# Power_Distro_Board_V5.net
KiCad netlist of a schematic drawn in EAGLE
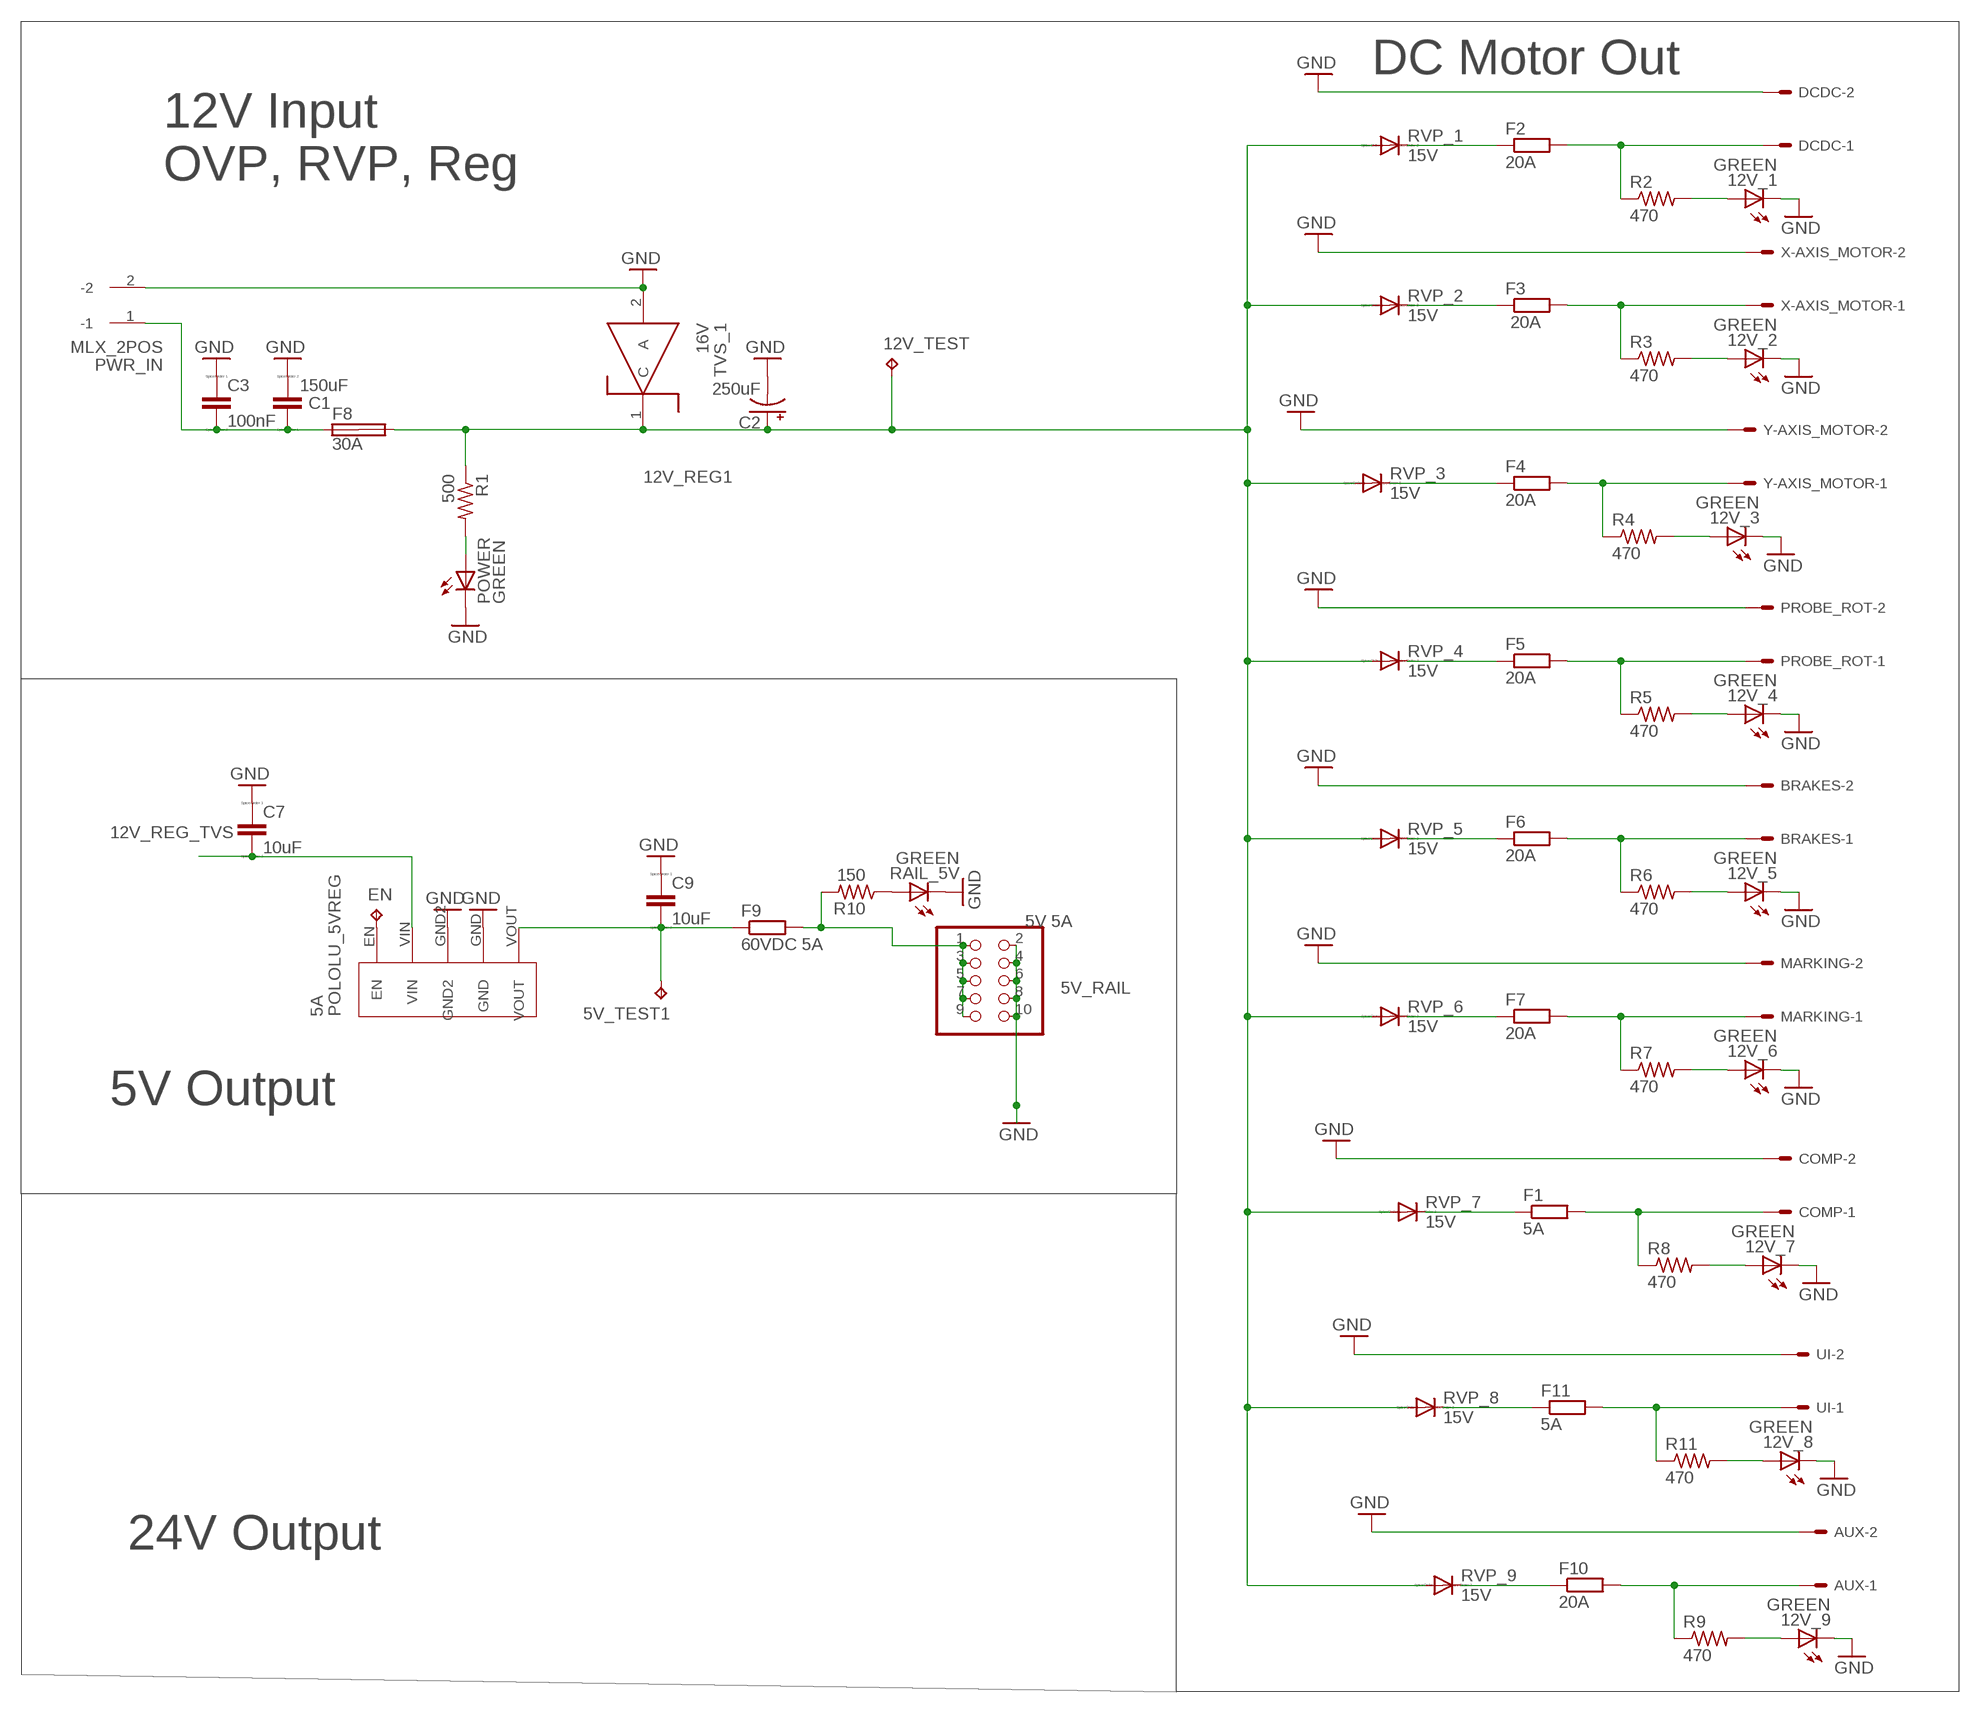
[diagram p0: schematic, sheet 1]

(export (version "E")
  (design (tool "Eeschema 10.0.6"))
  (components
    (comp (ref "5A")
      (value "POLOLU_5VREG")
      (footprint "eagle-import:SIP5")
      (libsource (lib "eagle-import") (part "POLOLU_5VREG"))
    )
    (comp (ref "5V_RAIL")
      (value "5V 5A")
      (footprint "eagle-import:2X05")
      (libsource (lib "eagle-import") (part "PINHD-2X5"))
    )
    (comp (ref "5V_TEST1")
      (value "TPPAD1-13")
      (footprint "eagle-import:P1-13")
      (libsource (lib "eagle-import") (part "TPPAD1-13"))
    )
    (comp (ref "12V_1")
      (value "GREEN")
      (footprint "eagle-import:SML1206")
      (libsource (lib "eagle-import") (part "LEDSML1206"))
    )
    (comp (ref "12V_2")
      (value "GREEN")
      (footprint "eagle-import:SML1206")
      (libsource (lib "eagle-import") (part "LEDSML1206"))
    )
    (comp (ref "12V_3")
      (value "GREEN")
      (footprint "eagle-import:SML1206")
      (libsource (lib "eagle-import") (part "LEDSML1206"))
    )
    (comp (ref "12V_4")
      (value "GREEN")
      (footprint "eagle-import:SML1206")
      (libsource (lib "eagle-import") (part "LEDSML1206"))
    )
    (comp (ref "12V_5")
      (value "GREEN")
      (footprint "eagle-import:SML1206")
      (libsource (lib "eagle-import") (part "LEDSML1206"))
    )
    (comp (ref "12V_6")
      (value "GREEN")
      (footprint "eagle-import:SML1206")
      (libsource (lib "eagle-import") (part "LEDSML1206"))
    )
    (comp (ref "12V_7")
      (value "GREEN")
      (footprint "eagle-import:SML1206")
      (libsource (lib "eagle-import") (part "LEDSML1206"))
    )
    (comp (ref "12V_8")
      (value "GREEN")
      (footprint "eagle-import:SML1206")
      (libsource (lib "eagle-import") (part "LEDSML1206"))
    )
    (comp (ref "12V_9")
      (value "GREEN")
      (footprint "eagle-import:SML1206")
      (libsource (lib "eagle-import") (part "LEDSML1206"))
    )
    (comp (ref "12V_TEST")
      (value "TPPAD1-13")
      (footprint "eagle-import:P1-13")
      (libsource (lib "eagle-import") (part "TPPAD1-13"))
    )
    (comp (ref "AUX")
      (value "555X-2V")
      (footprint "eagle-import:5566-2")
      (libsource (lib "eagle-import") (part "555X-2V"))
    )
    (comp (ref "BRAKES")
      (value "555X-2V")
      (footprint "eagle-import:5566-2")
      (libsource (lib "eagle-import") (part "555X-2V"))
    )
    (comp (ref "C1")
      (value "150uF")
      (footprint "eagle-import:C1210")
      (libsource (lib "eagle-import") (part "CC1210"))
    )
    (comp (ref "C2")
      (value "250uF")
      (footprint "eagle-import:CPOL-RADIAL-5MM-10MM")
      (libsource (lib "eagle-import") (part "ALUM_ELEC_RADIAL"))
    )
    (comp (ref "C3")
      (value "100nF")
      (footprint "eagle-import:C1210")
      (libsource (lib "eagle-import") (part "CC1210"))
    )
    (comp (ref "C7")
      (value "10uF")
      (footprint "eagle-import:C1210")
      (libsource (lib "eagle-import") (part "CC1210"))
    )
    (comp (ref "C9")
      (value "10uF")
      (footprint "eagle-import:C1210")
      (libsource (lib "eagle-import") (part "CC1210"))
    )
    (comp (ref "COMP")
      (value "555X-2V")
      (footprint "eagle-import:5566-2")
      (libsource (lib "eagle-import") (part "555X-2V"))
    )
    (comp (ref "DCDC")
      (value "555X-2V")
      (footprint "eagle-import:5566-2")
      (libsource (lib "eagle-import") (part "555X-2V"))
    )
    (comp (ref "EN")
      (value "TPPAD1-13")
      (footprint "eagle-import:P1-13")
      (libsource (lib "eagle-import") (part "TPPAD1-13"))
    )
    (comp (ref "F1")
      (value "5A")
      (footprint "eagle-import:M1206")
      (libsource (lib "eagle-import") (part "R-EU_M1206"))
    )
    (comp (ref "F2")
      (value "20A")
      (footprint "eagle-import:M1206")
      (libsource (lib "eagle-import") (part "R-EU_M1206"))
    )
    (comp (ref "F3")
      (value "20A")
      (footprint "eagle-import:M1206")
      (libsource (lib "eagle-import") (part "R-EU_M1206"))
    )
    (comp (ref "F4")
      (value "20A")
      (footprint "eagle-import:M1206")
      (libsource (lib "eagle-import") (part "R-EU_M1206"))
    )
    (comp (ref "F5")
      (value "20A")
      (footprint "eagle-import:M1206")
      (libsource (lib "eagle-import") (part "R-EU_M1206"))
    )
    (comp (ref "F6")
      (value "20A")
      (footprint "eagle-import:M1206")
      (libsource (lib "eagle-import") (part "R-EU_M1206"))
    )
    (comp (ref "F7")
      (value "20A")
      (footprint "eagle-import:M1206")
      (libsource (lib "eagle-import") (part "R-EU_M1206"))
    )
    (comp (ref "F8")
      (value "30A")
      (footprint "eagle-import:SHK20L")
      (libsource (lib "eagle-import") (part "SHK20L"))
    )
    (comp (ref "F9")
      (value "60VDC 5A")
      (footprint "eagle-import:M1206")
      (libsource (lib "eagle-import") (part "R-EU_M1206"))
    )
    (comp (ref "F10")
      (value "20A")
      (footprint "eagle-import:M1206")
      (libsource (lib "eagle-import") (part "R-EU_M1206"))
    )
    (comp (ref "F11")
      (value "5A")
      (footprint "eagle-import:M1206")
      (libsource (lib "eagle-import") (part "R-EU_M1206"))
    )
    (comp (ref "MARKING")
      (value "555X-2V")
      (footprint "eagle-import:5566-2")
      (libsource (lib "eagle-import") (part "555X-2V"))
    )
    (comp (ref "POWER")
      (value "GREEN")
      (footprint "eagle-import:SML1206")
      (libsource (lib "eagle-import") (part "LEDSML1206"))
    )
    (comp (ref "PROBE_ROT")
      (value "555X-2V")
      (footprint "eagle-import:5566-2")
      (libsource (lib "eagle-import") (part "555X-2V"))
    )
    (comp (ref "PWR_IN")
      (value "MLX_2POS")
      (footprint "eagle-import:.084MLX")
      (libsource (lib "eagle-import") (part "MLX_2POS"))
    )
    (comp (ref "R1")
      (value "500")
      (footprint "eagle-import:R1206")
      (libsource (lib "eagle-import") (part "R-US_R1206"))
    )
    (comp (ref "R2")
      (value "470")
      (footprint "eagle-import:R1206")
      (libsource (lib "eagle-import") (part "R-US_R1206"))
    )
    (comp (ref "R3")
      (value "470")
      (footprint "eagle-import:R1206")
      (libsource (lib "eagle-import") (part "R-US_R1206"))
    )
    (comp (ref "R4")
      (value "470")
      (footprint "eagle-import:R1206")
      (libsource (lib "eagle-import") (part "R-US_R1206"))
    )
    (comp (ref "R5")
      (value "470")
      (footprint "eagle-import:R1206")
      (libsource (lib "eagle-import") (part "R-US_R1206"))
    )
    (comp (ref "R6")
      (value "470")
      (footprint "eagle-import:R1206")
      (libsource (lib "eagle-import") (part "R-US_R1206"))
    )
    (comp (ref "R7")
      (value "470")
      (footprint "eagle-import:R1206")
      (libsource (lib "eagle-import") (part "R-US_R1206"))
    )
    (comp (ref "R8")
      (value "470")
      (footprint "eagle-import:R1206")
      (libsource (lib "eagle-import") (part "R-US_R1206"))
    )
    (comp (ref "R9")
      (value "470")
      (footprint "eagle-import:R1206")
      (libsource (lib "eagle-import") (part "R-US_R1206"))
    )
    (comp (ref "R10")
      (value "150")
      (footprint "eagle-import:R1206")
      (libsource (lib "eagle-import") (part "R-US_R1206"))
    )
    (comp (ref "R11")
      (value "470")
      (footprint "eagle-import:R1206")
      (libsource (lib "eagle-import") (part "R-US_R1206"))
    )
    (comp (ref "RAIL_5V")
      (value "GREEN")
      (footprint "eagle-import:SML1206")
      (libsource (lib "eagle-import") (part "LEDSML1206"))
    )
    (comp (ref "RVP_1")
      (value "15V")
      (footprint "eagle-import:TO220ACS")
      (libsource (lib "eagle-import") (part "BYT08P"))
    )
    (comp (ref "RVP_2")
      (value "15V")
      (footprint "eagle-import:TO220ACS")
      (libsource (lib "eagle-import") (part "BYT08P"))
    )
    (comp (ref "RVP_3")
      (value "15V")
      (footprint "eagle-import:TO220ACS")
      (libsource (lib "eagle-import") (part "BYT08P"))
    )
    (comp (ref "RVP_4")
      (value "15V")
      (footprint "eagle-import:TO220ACS")
      (libsource (lib "eagle-import") (part "BYT08P"))
    )
    (comp (ref "RVP_5")
      (value "15V")
      (footprint "eagle-import:TO220ACS")
      (libsource (lib "eagle-import") (part "BYT08P"))
    )
    (comp (ref "RVP_6")
      (value "15V")
      (footprint "eagle-import:TO220ACS")
      (libsource (lib "eagle-import") (part "BYT08P"))
    )
    (comp (ref "RVP_7")
      (value "15V")
      (footprint "eagle-import:TO220ACS")
      (libsource (lib "eagle-import") (part "BYT08P"))
    )
    (comp (ref "RVP_8")
      (value "15V")
      (footprint "eagle-import:TO220ACS")
      (libsource (lib "eagle-import") (part "BYT08P"))
    )
    (comp (ref "RVP_9")
      (value "15V")
      (footprint "eagle-import:TO220ACS")
      (libsource (lib "eagle-import") (part "BYT08P"))
    )
    (comp (ref "TVS_1")
      (value "16V")
      (footprint "eagle-import:DO-214AC")
      (libsource (lib "eagle-import") (part "SMAJ26A_TVSSMA"))
    )
    (comp (ref "UI")
      (value "555X-2V")
      (footprint "eagle-import:5566-2")
      (libsource (lib "eagle-import") (part "555X-2V"))
    )
    (comp (ref "X-AXIS_MOTOR")
      (value "555X-2V")
      (footprint "eagle-import:5566-2")
      (libsource (lib "eagle-import") (part "555X-2V"))
    )
    (comp (ref "Y-AXIS_MOTOR")
      (value "555X-2V")
      (footprint "eagle-import:5566-2")
      (libsource (lib "eagle-import") (part "555X-2V"))
    )
  )
  (nets
    (net (code "1") (name "/12V_REG1") (class "Default")
      (node (ref "12V_TEST") (pin "TP") (pinfunction "TP_TP") (pintype "input"))
      (node (ref "C2") (pin "+") (pinfunction "+_+") (pintype "passive"))
      (node (ref "F8") (pin "2A") (pinfunction "2A_2A") (pintype "passive"))
      (node (ref "R1") (pin "1") (pinfunction "1_1") (pintype "passive"))
      (node (ref "RVP_1") (pin "A") (pinfunction "A_A") (pintype "passive"))
      (node (ref "RVP_2") (pin "A") (pinfunction "A_A") (pintype "passive"))
      (node (ref "RVP_3") (pin "A") (pinfunction "A_A") (pintype "passive"))
      (node (ref "RVP_4") (pin "A") (pinfunction "A_A") (pintype "passive"))
      (node (ref "RVP_5") (pin "A") (pinfunction "A_A") (pintype "passive"))
      (node (ref "RVP_6") (pin "A") (pinfunction "A_A") (pintype "passive"))
      (node (ref "RVP_7") (pin "A") (pinfunction "A_A") (pintype "passive"))
      (node (ref "RVP_8") (pin "A") (pinfunction "A_A") (pintype "passive"))
      (node (ref "RVP_9") (pin "A") (pinfunction "A_A") (pintype "passive"))
      (node (ref "TVS_1") (pin "1") (pinfunction "C_1") (pintype "bidirectional"))
    )
    (net (code "2") (name "/12V_REG_TVS") (class "Default")
      (node (ref "5A") (pin "VIN") (pinfunction "VIN_VIN") (pintype "bidirectional"))
      (node (ref "C7") (pin "2") (pinfunction "2_2") (pintype "passive"))
    )
    (net (code "3") (name "GND") (class "Default")
      (node (ref "12V_1") (pin "C") (pinfunction "C_C") (pintype "passive"))
      (node (ref "12V_2") (pin "C") (pinfunction "C_C") (pintype "passive"))
      (node (ref "12V_3") (pin "C") (pinfunction "C_C") (pintype "passive"))
      (node (ref "12V_4") (pin "C") (pinfunction "C_C") (pintype "passive"))
      (node (ref "12V_5") (pin "C") (pinfunction "C_C") (pintype "passive"))
      (node (ref "12V_6") (pin "C") (pinfunction "C_C") (pintype "passive"))
      (node (ref "12V_7") (pin "C") (pinfunction "C_C") (pintype "passive"))
      (node (ref "12V_8") (pin "C") (pinfunction "C_C") (pintype "passive"))
      (node (ref "12V_9") (pin "C") (pinfunction "C_C") (pintype "passive"))
      (node (ref "5A") (pin "GND") (pinfunction "GND_GND") (pintype "bidirectional"))
      (node (ref "5A") (pin "GND2") (pinfunction "GND2_GND2") (pintype "bidirectional"))
      (node (ref "5V_RAIL") (pin "10") (pinfunction "10_10") (pintype "passive"))
      (node (ref "5V_RAIL") (pin "2") (pinfunction "2_2") (pintype "passive"))
      (node (ref "5V_RAIL") (pin "4") (pinfunction "4_4") (pintype "passive"))
      (node (ref "5V_RAIL") (pin "6") (pinfunction "6_6") (pintype "passive"))
      (node (ref "5V_RAIL") (pin "8") (pinfunction "8_8") (pintype "passive"))
      (node (ref "AUX") (pin "2") (pinfunction "S_2") (pintype "passive"))
      (node (ref "BRAKES") (pin "2") (pinfunction "S_2") (pintype "passive"))
      (node (ref "C1") (pin "2") (pinfunction "2_2") (pintype "passive"))
      (node (ref "C2") (pin "-") (pinfunction "-_-") (pintype "passive"))
      (node (ref "C3") (pin "1") (pinfunction "1_1") (pintype "passive"))
      (node (ref "C7") (pin "1") (pinfunction "1_1") (pintype "passive"))
      (node (ref "C9") (pin "1") (pinfunction "1_1") (pintype "passive"))
      (node (ref "COMP") (pin "2") (pinfunction "S_2") (pintype "passive"))
      (node (ref "DCDC") (pin "2") (pinfunction "S_2") (pintype "passive"))
      (node (ref "MARKING") (pin "2") (pinfunction "S_2") (pintype "passive"))
      (node (ref "POWER") (pin "C") (pinfunction "C_C") (pintype "passive"))
      (node (ref "PROBE_ROT") (pin "2") (pinfunction "S_2") (pintype "passive"))
      (node (ref "PWR_IN") (pin "2") (pinfunction "-2_2") (pintype "bidirectional"))
      (node (ref "RAIL_5V") (pin "C") (pinfunction "C_C") (pintype "passive"))
      (node (ref "TVS_1") (pin "2") (pinfunction "A_2") (pintype "bidirectional"))
      (node (ref "UI") (pin "2") (pinfunction "S_2") (pintype "passive"))
      (node (ref "X-AXIS_MOTOR") (pin "2") (pinfunction "S_2") (pintype "passive"))
      (node (ref "Y-AXIS_MOTOR") (pin "2") (pinfunction "S_2") (pintype "passive"))
    )
    (net (code "4") (name "Net-(5A-PadEN)") (class "Default")
      (node (ref "5A") (pin "EN") (pinfunction "EN_EN") (pintype "bidirectional"))
      (node (ref "EN") (pin "TP") (pinfunction "TP_TP") (pintype "input"))
    )
    (net (code "5") (name "Net-(5A-PadVOUT)") (class "Default")
      (node (ref "5A") (pin "VOUT") (pinfunction "VOUT_VOUT") (pintype "bidirectional"))
      (node (ref "5V_TEST1") (pin "TP") (pinfunction "TP_TP") (pintype "input"))
      (node (ref "C9") (pin "2") (pinfunction "2_2") (pintype "passive"))
      (node (ref "F9") (pin "1") (pinfunction "1_1") (pintype "passive"))
    )
    (net (code "6") (name "Net-(5V_RAIL-Pad1)") (class "Default")
      (node (ref "5V_RAIL") (pin "1") (pinfunction "1_1") (pintype "passive"))
      (node (ref "5V_RAIL") (pin "3") (pinfunction "3_3") (pintype "passive"))
      (node (ref "5V_RAIL") (pin "5") (pinfunction "5_5") (pintype "passive"))
      (node (ref "5V_RAIL") (pin "7") (pinfunction "7_7") (pintype "passive"))
      (node (ref "5V_RAIL") (pin "9") (pinfunction "9_9") (pintype "passive"))
      (node (ref "F9") (pin "2") (pinfunction "2_2") (pintype "passive"))
      (node (ref "R10") (pin "2") (pinfunction "2_2") (pintype "passive"))
    )
    (net (code "7") (name "Net-(12V_1-PadA)") (class "Default")
      (node (ref "12V_1") (pin "A") (pinfunction "A_A") (pintype "passive"))
      (node (ref "R2") (pin "2") (pinfunction "2_2") (pintype "passive"))
    )
    (net (code "8") (name "Net-(12V_2-PadA)") (class "Default")
      (node (ref "12V_2") (pin "A") (pinfunction "A_A") (pintype "passive"))
      (node (ref "R3") (pin "2") (pinfunction "2_2") (pintype "passive"))
    )
    (net (code "9") (name "Net-(12V_3-PadA)") (class "Default")
      (node (ref "12V_3") (pin "A") (pinfunction "A_A") (pintype "passive"))
      (node (ref "R4") (pin "2") (pinfunction "2_2") (pintype "passive"))
    )
    (net (code "10") (name "Net-(12V_4-PadA)") (class "Default")
      (node (ref "12V_4") (pin "A") (pinfunction "A_A") (pintype "passive"))
      (node (ref "R5") (pin "2") (pinfunction "2_2") (pintype "passive"))
    )
    (net (code "11") (name "Net-(12V_5-PadA)") (class "Default")
      (node (ref "12V_5") (pin "A") (pinfunction "A_A") (pintype "passive"))
      (node (ref "R6") (pin "2") (pinfunction "2_2") (pintype "passive"))
    )
    (net (code "12") (name "Net-(12V_6-PadA)") (class "Default")
      (node (ref "12V_6") (pin "A") (pinfunction "A_A") (pintype "passive"))
      (node (ref "R7") (pin "2") (pinfunction "2_2") (pintype "passive"))
    )
    (net (code "13") (name "Net-(12V_7-PadA)") (class "Default")
      (node (ref "12V_7") (pin "A") (pinfunction "A_A") (pintype "passive"))
      (node (ref "R8") (pin "2") (pinfunction "2_2") (pintype "passive"))
    )
    (net (code "14") (name "Net-(12V_8-PadA)") (class "Default")
      (node (ref "12V_8") (pin "A") (pinfunction "A_A") (pintype "passive"))
      (node (ref "R11") (pin "2") (pinfunction "2_2") (pintype "passive"))
    )
    (net (code "15") (name "Net-(12V_9-PadA)") (class "Default")
      (node (ref "12V_9") (pin "A") (pinfunction "A_A") (pintype "passive"))
      (node (ref "R9") (pin "2") (pinfunction "2_2") (pintype "passive"))
    )
    (net (code "16") (name "Net-(AUXA-S)") (class "Default")
      (node (ref "AUX") (pin "1") (pinfunction "S_1") (pintype "passive"))
      (node (ref "F10") (pin "2") (pinfunction "2_2") (pintype "passive"))
      (node (ref "R9") (pin "1") (pinfunction "1_1") (pintype "passive"))
    )
    (net (code "17") (name "Net-(BRAKESA-S)") (class "Default")
      (node (ref "BRAKES") (pin "1") (pinfunction "S_1") (pintype "passive"))
      (node (ref "F6") (pin "2") (pinfunction "2_2") (pintype "passive"))
      (node (ref "R6") (pin "1") (pinfunction "1_1") (pintype "passive"))
    )
    (net (code "18") (name "Net-(COMPA-S)") (class "Default")
      (node (ref "COMP") (pin "1") (pinfunction "S_1") (pintype "passive"))
      (node (ref "F1") (pin "2") (pinfunction "2_2") (pintype "passive"))
      (node (ref "R8") (pin "1") (pinfunction "1_1") (pintype "passive"))
    )
    (net (code "19") (name "Net-(DCDCA-S)") (class "Default")
      (node (ref "DCDC") (pin "1") (pinfunction "S_1") (pintype "passive"))
      (node (ref "F2") (pin "2") (pinfunction "2_2") (pintype "passive"))
      (node (ref "R2") (pin "1") (pinfunction "1_1") (pintype "passive"))
    )
    (net (code "20") (name "Net-(F1-Pad1)") (class "Default")
      (node (ref "F1") (pin "1") (pinfunction "1_1") (pintype "passive"))
      (node (ref "RVP_7") (pin "C") (pinfunction "C_C") (pintype "passive"))
    )
    (net (code "21") (name "Net-(F2-Pad1)") (class "Default")
      (node (ref "F2") (pin "1") (pinfunction "1_1") (pintype "passive"))
      (node (ref "RVP_1") (pin "C") (pinfunction "C_C") (pintype "passive"))
    )
    (net (code "22") (name "Net-(F3-Pad1)") (class "Default")
      (node (ref "F3") (pin "1") (pinfunction "1_1") (pintype "passive"))
      (node (ref "RVP_2") (pin "C") (pinfunction "C_C") (pintype "passive"))
    )
    (net (code "23") (name "Net-(F4-Pad1)") (class "Default")
      (node (ref "F4") (pin "1") (pinfunction "1_1") (pintype "passive"))
      (node (ref "RVP_3") (pin "C") (pinfunction "C_C") (pintype "passive"))
    )
    (net (code "24") (name "Net-(F5-Pad1)") (class "Default")
      (node (ref "F5") (pin "1") (pinfunction "1_1") (pintype "passive"))
      (node (ref "RVP_4") (pin "C") (pinfunction "C_C") (pintype "passive"))
    )
    (net (code "25") (name "Net-(F6-Pad1)") (class "Default")
      (node (ref "F6") (pin "1") (pinfunction "1_1") (pintype "passive"))
      (node (ref "RVP_5") (pin "C") (pinfunction "C_C") (pintype "passive"))
    )
    (net (code "26") (name "Net-(F7-Pad1)") (class "Default")
      (node (ref "F7") (pin "1") (pinfunction "1_1") (pintype "passive"))
      (node (ref "RVP_6") (pin "C") (pinfunction "C_C") (pintype "passive"))
    )
    (net (code "27") (name "Net-(F10-Pad1)") (class "Default")
      (node (ref "F10") (pin "1") (pinfunction "1_1") (pintype "passive"))
      (node (ref "RVP_9") (pin "C") (pinfunction "C_C") (pintype "passive"))
    )
    (net (code "28") (name "Net-(F11-Pad1)") (class "Default")
      (node (ref "F11") (pin "1") (pinfunction "1_1") (pintype "passive"))
      (node (ref "RVP_8") (pin "C") (pinfunction "C_C") (pintype "passive"))
    )
    (net (code "29") (name "Net-(MARKINGA-S)") (class "Default")
      (node (ref "F7") (pin "2") (pinfunction "2_2") (pintype "passive"))
      (node (ref "MARKING") (pin "1") (pinfunction "S_1") (pintype "passive"))
      (node (ref "R7") (pin "1") (pinfunction "1_1") (pintype "passive"))
    )
    (net (code "30") (name "Net-(POWER-PadA)") (class "Default")
      (node (ref "POWER") (pin "A") (pinfunction "A_A") (pintype "passive"))
      (node (ref "R1") (pin "2") (pinfunction "2_2") (pintype "passive"))
    )
    (net (code "31") (name "Net-(PROBE_ROTA-S)") (class "Default")
      (node (ref "F5") (pin "2") (pinfunction "2_2") (pintype "passive"))
      (node (ref "PROBE_ROT") (pin "1") (pinfunction "S_1") (pintype "passive"))
      (node (ref "R5") (pin "1") (pinfunction "1_1") (pintype "passive"))
    )
    (net (code "32") (name "Net-(PWR_IN--1)") (class "Default")
      (node (ref "C1") (pin "1") (pinfunction "1_1") (pintype "passive"))
      (node (ref "C3") (pin "2") (pinfunction "2_2") (pintype "passive"))
      (node (ref "F8") (pin "1A") (pinfunction "1A_1A") (pintype "passive"))
      (node (ref "PWR_IN") (pin "1") (pinfunction "-1_1") (pintype "bidirectional"))
    )
    (net (code "33") (name "Net-(R10-Pad1)") (class "Default")
      (node (ref "R10") (pin "1") (pinfunction "1_1") (pintype "passive"))
      (node (ref "RAIL_5V") (pin "A") (pinfunction "A_A") (pintype "passive"))
    )
    (net (code "34") (name "Net-(UIA-S)") (class "Default")
      (node (ref "F11") (pin "2") (pinfunction "2_2") (pintype "passive"))
      (node (ref "R11") (pin "1") (pinfunction "1_1") (pintype "passive"))
      (node (ref "UI") (pin "1") (pinfunction "S_1") (pintype "passive"))
    )
    (net (code "35") (name "Net-(X-AXIS_MOTORA-S)") (class "Default")
      (node (ref "F3") (pin "2") (pinfunction "2_2") (pintype "passive"))
      (node (ref "R3") (pin "1") (pinfunction "1_1") (pintype "passive"))
      (node (ref "X-AXIS_MOTOR") (pin "1") (pinfunction "S_1") (pintype "passive"))
    )
    (net (code "36") (name "Net-(Y-AXIS_MOTORA-S)") (class "Default")
      (node (ref "F4") (pin "2") (pinfunction "2_2") (pintype "passive"))
      (node (ref "R4") (pin "1") (pinfunction "1_1") (pintype "passive"))
      (node (ref "Y-AXIS_MOTOR") (pin "1") (pinfunction "S_1") (pintype "passive"))
    )
    (net (code "37") (name "unconnected-(F8-Pad1B)") (class "Default")
      (node (ref "F8") (pin "1B") (pinfunction "1B_1B") (pintype "passive"))
    )
    (net (code "38") (name "unconnected-(F8-Pad2B)") (class "Default")
      (node (ref "F8") (pin "2B") (pinfunction "2B_2B") (pintype "passive"))
    )
  )
)
